# Schematic.net
KiCad netlist of a schematic drawn in Altium Designer
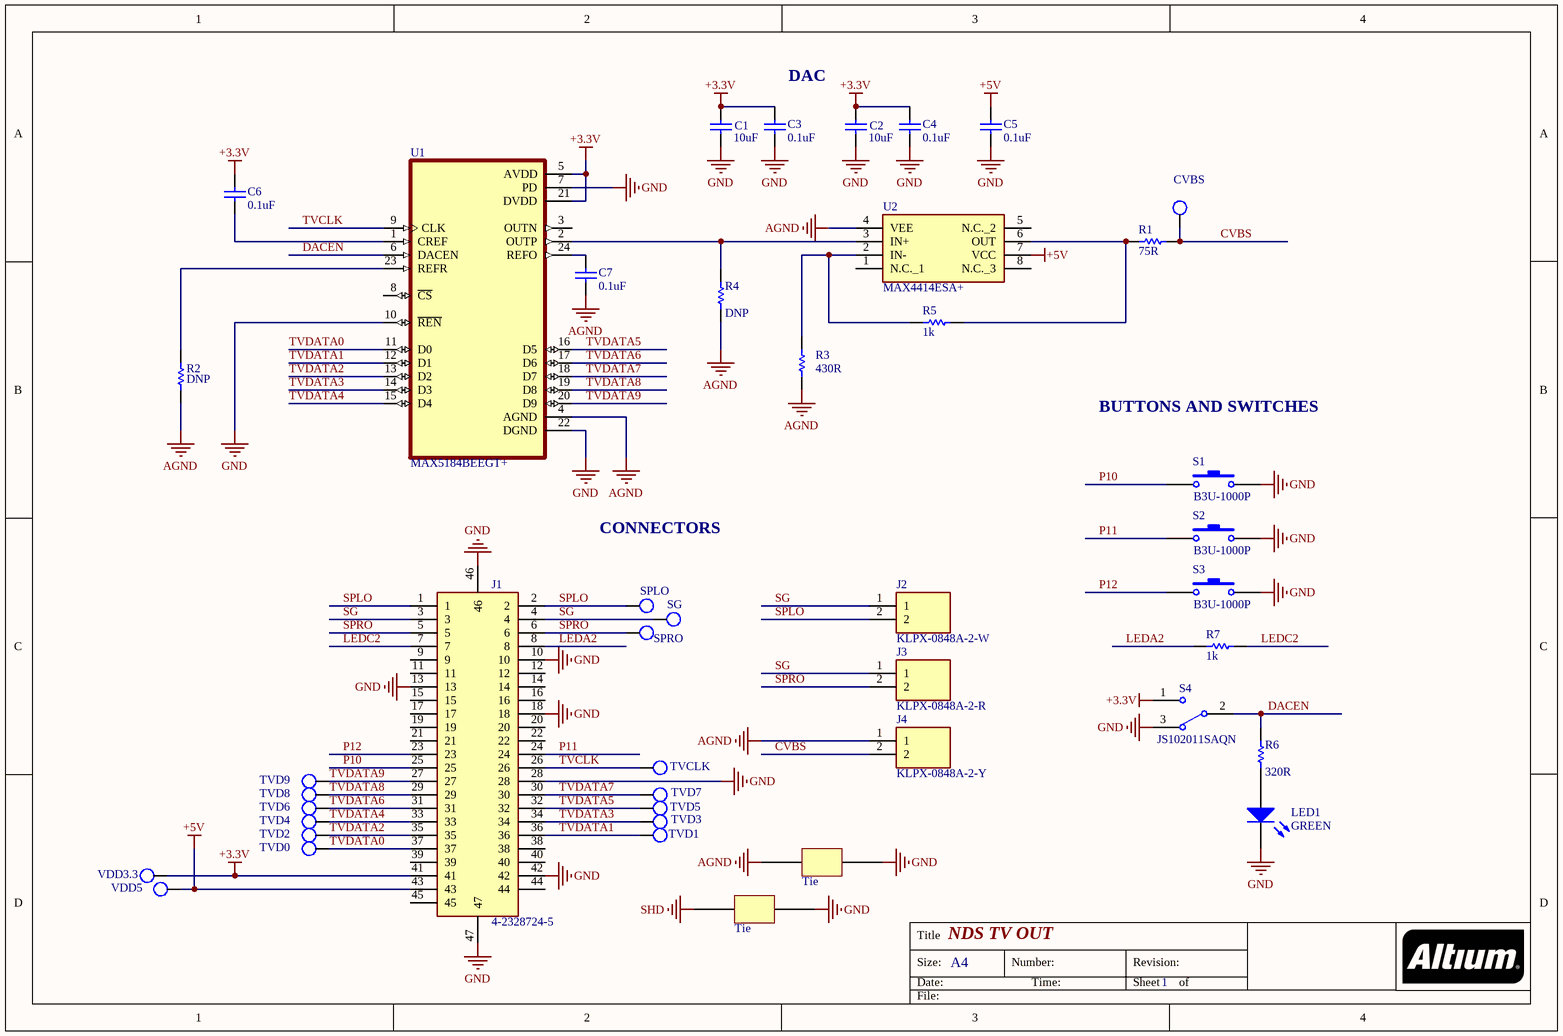
[diagram p0: Schematic.SchDoc]

(export (version "E")
  (design (tool "Eeschema 10.0.6"))
  (components
    (comp (ref "C1")
      (value "10uF")
      (footprint "CAPC2012X90N")
      (description "Capacitor")
      (fields (field (name "PUBLISHER") "Altium Limited"))
      (libsource (lib "Miscellaneous Devices") (part "Cap"))
    )
    (comp (ref "C2")
      (value "10uF")
      (footprint "CAPC2012X90N")
      (description "Capacitor")
      (fields (field (name "PUBLISHER") "Altium Limited"))
      (libsource (lib "Miscellaneous Devices") (part "Cap"))
    )
    (comp (ref "C3")
      (value "0.1uF")
      (footprint "CAPC2012X90N")
      (description "Capacitor")
      (fields (field (name "PUBLISHER") "Altium Limited"))
      (libsource (lib "Miscellaneous Devices") (part "Cap"))
    )
    (comp (ref "C4")
      (value "0.1uF")
      (footprint "CAPC2012X90N")
      (description "Capacitor")
      (fields (field (name "PUBLISHER") "Altium Limited"))
      (libsource (lib "Miscellaneous Devices") (part "Cap"))
    )
    (comp (ref "C5")
      (value "0.1uF")
      (footprint "CAPC2012X90N")
      (description "Capacitor")
      (fields (field (name "PUBLISHER") "Altium Limited"))
      (libsource (lib "Miscellaneous Devices") (part "Cap"))
    )
    (comp (ref "C6")
      (value "0.1uF")
      (footprint "CAPC2012X90N")
      (description "Capacitor")
      (fields (field (name "PUBLISHER") "Altium Limited"))
      (libsource (lib "Miscellaneous Devices") (part "Cap"))
    )
    (comp (ref "C7")
      (value "0.1uF")
      (footprint "CAPC2012X90N")
      (description "Capacitor")
      (fields (field (name "PUBLISHER") "Altium Limited"))
      (libsource (lib "Miscellaneous Devices") (part "Cap"))
    )
    (comp (ref "CVBS")
      (value "~")
      (footprint "Test_Point")
      (description "Test Point")
      (libsource (lib "*") (part "TP_P0_0.8_D0"))
    )
    (comp (ref "J1")
      (value "4-2328724-5")
      (footprint "SamacSys:423287245")
      (description "Connector")
      (fields (field (name "MOUSER PART NUMBER") "571-4-2328724-5"))
      (libsource (lib "*") (part "4-2328724-5"))
    )
    (comp (ref "J2")
      (value "KLPX-0848A-2-W")
      (footprint "SamacSys:KLPX0848A2RG")
      (description "Connector")
      (fields
        (field (name "MANUFACTURER_PART_NUMBER") "KLPX-0848A-2-R-G")
        (field (name "MOUSER PART NUMBER") "806-KLPX-0848A-2RG")
      )
      (libsource (lib "*") (part "KLPX-0848A-2-R-G"))
    )
    (comp (ref "J3")
      (value "KLPX-0848A-2-R")
      (footprint "SamacSys:KLPX0848A2RG")
      (description "Connector")
      (fields
        (field (name "MANUFACTURER_PART_NUMBER") "KLPX-0848A-2-R-G")
        (field (name "MOUSER PART NUMBER") "806-KLPX-0848A-2RG")
      )
      (libsource (lib "*") (part "KLPX-0848A-2-R-G"))
    )
    (comp (ref "J4")
      (value "KLPX-0848A-2-Y")
      (footprint "SamacSys:KLPX0848A2RG")
      (description "Connector")
      (fields
        (field (name "MANUFACTURER_PART_NUMBER") "KLPX-0848A-2-R-G")
        (field (name "MOUSER PART NUMBER") "806-KLPX-0848A-2RG")
      )
      (libsource (lib "*") (part "KLPX-0848A-2-R-G"))
    )
    (comp (ref "LED1")
      (value "GREEN")
      (footprint "LED_OSRAM_LOR976")
      (description "LED GREEN CLEAR 0603 SMD")
      (fields (field (name "MANUFACTURER") "Lite-On Inc.") (field (name "PUBLISHER") "Altium Limited"))
      (libsource (lib "Miscellaneous Devices") (part "LED0"))
    )
    (comp (ref "R1")
      (value "75R")
      (footprint "RESC2012X50N")
      (description "Resistor")
      (fields (field (name "Comment") "Res1") (field (name "PUBLISHER") "Altium Limited"))
      (libsource (lib "Miscellaneous Devices") (part "Res1"))
    )
    (comp (ref "R2")
      (value "DNP")
      (footprint "RESC2012X50N")
      (description "Resistor")
      (fields (field (name "Comment") "Res1") (field (name "PUBLISHER") "Altium Limited"))
      (libsource (lib "Miscellaneous Devices") (part "Res1"))
    )
    (comp (ref "R3")
      (value "430R")
      (footprint "RESC2012X50N")
      (description "Resistor")
      (fields (field (name "Comment") "Res1") (field (name "PUBLISHER") "Altium Limited"))
      (libsource (lib "Miscellaneous Devices") (part "Res1"))
    )
    (comp (ref "R4")
      (value "DNP")
      (footprint "RESC2012X50N")
      (description "Resistor")
      (fields (field (name "Comment") "Res1") (field (name "PUBLISHER") "Altium Limited"))
      (libsource (lib "Miscellaneous Devices") (part "Res1"))
    )
    (comp (ref "R5")
      (value "1k")
      (footprint "RESC2012X50N")
      (description "Resistor")
      (fields (field (name "Comment") "Res1") (field (name "PUBLISHER") "Altium Limited"))
      (libsource (lib "Miscellaneous Devices") (part "Res1"))
    )
    (comp (ref "R6")
      (value "320R")
      (footprint "RESC2012X50N")
      (description "Resistor")
      (fields (field (name "Comment") "Res1") (field (name "PUBLISHER") "Altium Limited"))
      (libsource (lib "Miscellaneous Devices") (part "Res1"))
    )
    (comp (ref "R7")
      (value "1k")
      (footprint "RESC2012X50N")
      (description "Resistor")
      (fields (field (name "Comment") "Res1") (field (name "PUBLISHER") "Altium Limited"))
      (libsource (lib "Miscellaneous Devices") (part "Res1"))
    )
    (comp (ref "S1")
      (value "B3U-1000P")
      (footprint "B3U-1000P")
      (description "Switch")
      (fields (field (name "PUBLISHER") "Altium Limited"))
      (libsource (lib "Miscellaneous Devices") (part "SW-PB"))
    )
    (comp (ref "S2")
      (value "B3U-1000P")
      (footprint "B3U-1000P")
      (description "Switch")
      (fields (field (name "PUBLISHER") "Altium Limited"))
      (libsource (lib "Miscellaneous Devices") (part "SW-PB"))
    )
    (comp (ref "S3")
      (value "B3U-1000P")
      (footprint "B3U-1000P")
      (description "Switch")
      (fields (field (name "PUBLISHER") "Altium Limited"))
      (libsource (lib "Miscellaneous Devices") (part "SW-PB"))
    )
    (comp (ref "S4")
      (value "JS102011SAQN")
      (footprint "JS102011SAQN")
      (description "SPDT Subminiature Toggle Switch, Right Angle Mounting, Vertical Actuation")
      (libsource (lib "Miscellaneous Devices") (part "SW-SPDT"))
    )
    (comp (ref "SG")
      (value "~")
      (footprint "Test_Point")
      (description "Test Point")
      (libsource (lib "*") (part "TP_P0_0.8_D0"))
    )
    (comp (ref "SPLO")
      (value "~")
      (footprint "Test_Point")
      (description "Test Point")
      (libsource (lib "*") (part "TP_P0_0.8_D0"))
    )
    (comp (ref "SPRO")
      (value "~")
      (footprint "Test_Point")
      (description "Test Point")
      (libsource (lib "*") (part "TP_P0_0.8_D0"))
    )
    (comp (ref "Tie1") (value "Tie") (footprint "Tie") (libsource (lib "MAX5184BEEGT") (part "Tie")))
    (comp (ref "Tie2") (value "Tie") (footprint "Tie") (libsource (lib "MAX5184BEEGT") (part "Tie")))
    (comp (ref "TVCLK")
      (value "~")
      (footprint "Test_Point")
      (description "Test Point")
      (libsource (lib "*") (part "TP_P0_0.8_D0"))
    )
    (comp (ref "TVD0")
      (value "~")
      (footprint "Test_Point")
      (description "Test Point")
      (libsource (lib "*") (part "TP_P0_0.8_D0"))
    )
    (comp (ref "TVD1")
      (value "~")
      (footprint "Test_Point")
      (description "Test Point")
      (libsource (lib "*") (part "TP_P0_0.8_D0"))
    )
    (comp (ref "TVD2")
      (value "~")
      (footprint "Test_Point")
      (description "Test Point")
      (libsource (lib "*") (part "TP_P0_0.8_D0"))
    )
    (comp (ref "TVD3")
      (value "~")
      (footprint "Test_Point")
      (description "Test Point")
      (libsource (lib "*") (part "TP_P0_0.8_D0"))
    )
    (comp (ref "TVD4")
      (value "~")
      (footprint "Test_Point")
      (description "Test Point")
      (libsource (lib "*") (part "TP_P0_0.8_D0"))
    )
    (comp (ref "TVD5")
      (value "~")
      (footprint "Test_Point")
      (description "Test Point")
      (libsource (lib "*") (part "TP_P0_0.8_D0"))
    )
    (comp (ref "TVD6")
      (value "~")
      (footprint "Test_Point")
      (description "Test Point")
      (libsource (lib "*") (part "TP_P0_0.8_D0"))
    )
    (comp (ref "TVD7")
      (value "~")
      (footprint "Test_Point")
      (description "Test Point")
      (libsource (lib "*") (part "TP_P0_0.8_D0"))
    )
    (comp (ref "TVD8")
      (value "~")
      (footprint "Test_Point")
      (description "Test Point")
      (libsource (lib "*") (part "TP_P0_0.8_D0"))
    )
    (comp (ref "TVD9")
      (value "~")
      (footprint "Test_Point")
      (description "Test Point")
      (libsource (lib "*") (part "TP_P0_0.8_D0"))
    )
    (comp (ref "U1")
      (value "MAX5184BEEGT+")
      (footprint "SOP63P602X175-24N")
      (fields (field (name "MP") "MAX5184BEEGT"))
      (libsource (lib "MAX5184BEEGT") (part "MAX5184BEEGT"))
    )
    (comp (ref "U2")
      (value "MAX4414ESA+")
      (footprint "SOIC127P600X175-8N")
      (description "Integrated Circuit")
      (fields (field (name "MOUSER PART NUMBER") "700-MAX4414ESA"))
      (libsource (lib "*") (part "MAX4414ESA+"))
    )
    (comp (ref "VDD3.3")
      (value "~")
      (footprint "Test_Point")
      (description "Test Point")
      (libsource (lib "*") (part "TP_P0_0.8_D0"))
    )
    (comp (ref "VDD5")
      (value "~")
      (footprint "Test_Point")
      (description "Test Point")
      (libsource (lib "*") (part "TP_P0_0.8_D0"))
    )
  )
  (nets
    (net (code "1") (name "+3.3V") (class "Default")
      (node (ref "C1") (pin "1") (pinfunction "1_1") (pintype "passive"))
      (node (ref "C2") (pin "1") (pinfunction "1_1") (pintype "passive"))
      (node (ref "C3") (pin "1") (pinfunction "1_1") (pintype "passive"))
      (node (ref "C4") (pin "1") (pinfunction "1_1") (pintype "passive"))
      (node (ref "C6") (pin "1") (pinfunction "1_1") (pintype "passive"))
      (node (ref "J1") (pin "41") (pinfunction "41_41") (pintype "passive"))
      (node (ref "S4") (pin "1") (pinfunction "1_1") (pintype "passive"))
      (node (ref "U1") (pin "21") (pinfunction "DVDD_21") (pintype "power_in"))
      (node (ref "U1") (pin "5") (pinfunction "AVDD_5") (pintype "power_in"))
      (node (ref "VDD3.3") (pin "1") (pinfunction "1_1") (pintype "passive"))
    )
    (net (code "2") (name "+5V") (class "Default")
      (node (ref "C5") (pin "1") (pinfunction "1_1") (pintype "passive"))
      (node (ref "J1") (pin "43") (pinfunction "43_43") (pintype "passive"))
      (node (ref "U2") (pin "7") (pinfunction "VCC_7") (pintype "passive"))
      (node (ref "VDD5") (pin "1") (pinfunction "1_1") (pintype "passive"))
    )
    (net (code "3") (name "/CVBS") (class "Default")
      (node (ref "CVBS") (pin "1") (pinfunction "1_1") (pintype "passive"))
      (node (ref "J4") (pin "2") (pinfunction "2_2") (pintype "passive"))
      (node (ref "R1") (pin "1") (pinfunction "1_1") (pintype "passive"))
    )
    (net (code "4") (name "/DACEN") (class "Default")
      (node (ref "R6") (pin "2") (pinfunction "2_2") (pintype "passive"))
      (node (ref "S4") (pin "2") (pinfunction "2_2") (pintype "passive"))
      (node (ref "U1") (pin "6") (pinfunction "DACEN_6") (pintype "input"))
    )
    (net (code "5") (name "/LEDA2") (class "Default")
      (node (ref "J1") (pin "8") (pinfunction "8_8") (pintype "passive"))
      (node (ref "R7") (pin "2") (pinfunction "2_2") (pintype "passive"))
    )
    (net (code "6") (name "/LEDC2") (class "Default")
      (node (ref "J1") (pin "7") (pinfunction "7_7") (pintype "passive"))
      (node (ref "R7") (pin "1") (pinfunction "1_1") (pintype "passive"))
    )
    (net (code "7") (name "/P10") (class "Default")
      (node (ref "J1") (pin "25") (pinfunction "25_25") (pintype "passive"))
      (node (ref "S1") (pin "1") (pinfunction "1_1") (pintype "passive"))
    )
    (net (code "8") (name "/P11") (class "Default")
      (node (ref "J1") (pin "24") (pinfunction "24_24") (pintype "passive"))
      (node (ref "S2") (pin "1") (pinfunction "1_1") (pintype "passive"))
    )
    (net (code "9") (name "/P12") (class "Default")
      (node (ref "J1") (pin "23") (pinfunction "23_23") (pintype "passive"))
      (node (ref "S3") (pin "1") (pinfunction "1_1") (pintype "passive"))
    )
    (net (code "10") (name "/SG") (class "Default")
      (node (ref "J1") (pin "3") (pinfunction "3_3") (pintype "passive"))
      (node (ref "J1") (pin "4") (pinfunction "4_4") (pintype "passive"))
      (node (ref "J2") (pin "1") (pinfunction "1_1") (pintype "passive"))
      (node (ref "J3") (pin "1") (pinfunction "1_1") (pintype "passive"))
      (node (ref "SG") (pin "1") (pinfunction "1_1") (pintype "passive"))
    )
    (net (code "11") (name "/SPLO") (class "Default")
      (node (ref "J1") (pin "1") (pinfunction "1_1") (pintype "passive"))
      (node (ref "J1") (pin "2") (pinfunction "2_2") (pintype "passive"))
      (node (ref "J2") (pin "2") (pinfunction "2_2") (pintype "passive"))
      (node (ref "SPLO") (pin "1") (pinfunction "1_1") (pintype "passive"))
    )
    (net (code "12") (name "/SPRO") (class "Default")
      (node (ref "J1") (pin "5") (pinfunction "5_5") (pintype "passive"))
      (node (ref "J1") (pin "6") (pinfunction "6_6") (pintype "passive"))
      (node (ref "J3") (pin "2") (pinfunction "2_2") (pintype "passive"))
      (node (ref "SPRO") (pin "1") (pinfunction "1_1") (pintype "passive"))
    )
    (net (code "13") (name "/TVCLK") (class "Default")
      (node (ref "J1") (pin "26") (pinfunction "26_26") (pintype "passive"))
      (node (ref "TVCLK") (pin "1") (pinfunction "1_1") (pintype "passive"))
      (node (ref "U1") (pin "9") (pinfunction "CLK_9") (pintype "input"))
    )
    (net (code "14") (name "/TVDATA0") (class "Default")
      (node (ref "J1") (pin "37") (pinfunction "37_37") (pintype "passive"))
      (node (ref "TVD0") (pin "1") (pinfunction "1_1") (pintype "passive"))
      (node (ref "U1") (pin "11") (pinfunction "D0_11") (pintype "bidirectional"))
    )
    (net (code "15") (name "/TVDATA1") (class "Default")
      (node (ref "J1") (pin "36") (pinfunction "36_36") (pintype "passive"))
      (node (ref "TVD1") (pin "1") (pinfunction "1_1") (pintype "passive"))
      (node (ref "U1") (pin "12") (pinfunction "D1_12") (pintype "bidirectional"))
    )
    (net (code "16") (name "/TVDATA2") (class "Default")
      (node (ref "J1") (pin "35") (pinfunction "35_35") (pintype "passive"))
      (node (ref "TVD2") (pin "1") (pinfunction "1_1") (pintype "passive"))
      (node (ref "U1") (pin "13") (pinfunction "D2_13") (pintype "bidirectional"))
    )
    (net (code "17") (name "/TVDATA3") (class "Default")
      (node (ref "J1") (pin "34") (pinfunction "34_34") (pintype "passive"))
      (node (ref "TVD3") (pin "1") (pinfunction "1_1") (pintype "passive"))
      (node (ref "U1") (pin "14") (pinfunction "D3_14") (pintype "bidirectional"))
    )
    (net (code "18") (name "/TVDATA4") (class "Default")
      (node (ref "J1") (pin "33") (pinfunction "33_33") (pintype "passive"))
      (node (ref "TVD4") (pin "1") (pinfunction "1_1") (pintype "passive"))
      (node (ref "U1") (pin "15") (pinfunction "D4_15") (pintype "bidirectional"))
    )
    (net (code "19") (name "/TVDATA5") (class "Default")
      (node (ref "J1") (pin "32") (pinfunction "32_32") (pintype "passive"))
      (node (ref "TVD5") (pin "1") (pinfunction "1_1") (pintype "passive"))
      (node (ref "U1") (pin "16") (pinfunction "D5_16") (pintype "bidirectional"))
    )
    (net (code "20") (name "/TVDATA6") (class "Default")
      (node (ref "J1") (pin "31") (pinfunction "31_31") (pintype "passive"))
      (node (ref "TVD6") (pin "1") (pinfunction "1_1") (pintype "passive"))
      (node (ref "U1") (pin "17") (pinfunction "D6_17") (pintype "bidirectional"))
    )
    (net (code "21") (name "/TVDATA7") (class "Default")
      (node (ref "J1") (pin "30") (pinfunction "30_30") (pintype "passive"))
      (node (ref "TVD7") (pin "1") (pinfunction "1_1") (pintype "passive"))
      (node (ref "U1") (pin "18") (pinfunction "D7_18") (pintype "bidirectional"))
    )
    (net (code "22") (name "/TVDATA8") (class "Default")
      (node (ref "J1") (pin "29") (pinfunction "29_29") (pintype "passive"))
      (node (ref "TVD8") (pin "1") (pinfunction "1_1") (pintype "passive"))
      (node (ref "U1") (pin "19") (pinfunction "D8_19") (pintype "bidirectional"))
    )
    (net (code "23") (name "/TVDATA9") (class "Default")
      (node (ref "J1") (pin "27") (pinfunction "27_27") (pintype "passive"))
      (node (ref "TVD9") (pin "1") (pinfunction "1_1") (pintype "passive"))
      (node (ref "U1") (pin "20") (pinfunction "D9_20") (pintype "bidirectional"))
    )
    (net (code "24") (name "AGND") (class "Default")
      (node (ref "C7") (pin "2") (pinfunction "2_2") (pintype "passive"))
      (node (ref "J4") (pin "1") (pinfunction "1_1") (pintype "passive"))
      (node (ref "R2") (pin "1") (pinfunction "1_1") (pintype "passive"))
      (node (ref "R3") (pin "1") (pinfunction "1_1") (pintype "passive"))
      (node (ref "R4") (pin "1") (pinfunction "1_1") (pintype "passive"))
      (node (ref "Tie1") (pin "1") (pinfunction "1_1") (pintype "passive"))
      (node (ref "U1") (pin "4") (pinfunction "AGND_4") (pintype "power_in"))
      (node (ref "U2") (pin "4") (pinfunction "VEE_4") (pintype "passive"))
    )
    (net (code "25") (name "GND") (class "Default")
      (node (ref "C1") (pin "2") (pinfunction "2_2") (pintype "passive"))
      (node (ref "C2") (pin "2") (pinfunction "2_2") (pintype "passive"))
      (node (ref "C3") (pin "2") (pinfunction "2_2") (pintype "passive"))
      (node (ref "C4") (pin "2") (pinfunction "2_2") (pintype "passive"))
      (node (ref "C5") (pin "2") (pinfunction "2_2") (pintype "passive"))
      (node (ref "J1") (pin "10") (pinfunction "10_10") (pintype "passive"))
      (node (ref "J1") (pin "13") (pinfunction "13_13") (pintype "passive"))
      (node (ref "J1") (pin "18") (pinfunction "18_18") (pintype "passive"))
      (node (ref "J1") (pin "28") (pinfunction "28_28") (pintype "passive"))
      (node (ref "J1") (pin "42") (pinfunction "42_42") (pintype "passive"))
      (node (ref "J1") (pin "46") (pinfunction "46_46") (pintype "passive"))
      (node (ref "J1") (pin "47") (pinfunction "47_47") (pintype "passive"))
      (node (ref "LED1") (pin "2") (pinfunction "K_2") (pintype "passive"))
      (node (ref "S1") (pin "2") (pinfunction "2_2") (pintype "passive"))
      (node (ref "S2") (pin "2") (pinfunction "2_2") (pintype "passive"))
      (node (ref "S3") (pin "2") (pinfunction "2_2") (pintype "passive"))
      (node (ref "S4") (pin "3") (pinfunction "3_3") (pintype "passive"))
      (node (ref "Tie1") (pin "2") (pinfunction "2_2") (pintype "passive"))
      (node (ref "Tie2") (pin "2") (pinfunction "2_2") (pintype "passive"))
      (node (ref "U1") (pin "10") (pinfunction "~{REN}_10") (pintype "bidirectional"))
      (node (ref "U1") (pin "22") (pinfunction "DGND_22") (pintype "power_in"))
      (node (ref "U1") (pin "7") (pinfunction "PD_7") (pintype "power_in"))
    )
    (net (code "26") (name "Net-(LED1-A)") (class "Default")
      (node (ref "LED1") (pin "1") (pinfunction "A_1") (pintype "passive"))
      (node (ref "R6") (pin "1") (pinfunction "1_1") (pintype "passive"))
    )
    (net (code "27") (name "Net-(U1-CREF)") (class "Default")
      (node (ref "C6") (pin "2") (pinfunction "2_2") (pintype "passive"))
      (node (ref "U1") (pin "1") (pinfunction "CREF_1") (pintype "input"))
    )
    (net (code "28") (name "Net-(U1-OUTP)") (class "Default")
      (node (ref "R4") (pin "2") (pinfunction "2_2") (pintype "passive"))
      (node (ref "U1") (pin "2") (pinfunction "OUTP_2") (pintype "output"))
      (node (ref "U2") (pin "3") (pinfunction "IN+_3") (pintype "passive"))
    )
    (net (code "29") (name "Net-(U1-REFO)") (class "Default")
      (node (ref "C7") (pin "1") (pinfunction "1_1") (pintype "passive"))
      (node (ref "U1") (pin "24") (pinfunction "REFO_24") (pintype "output"))
    )
    (net (code "30") (name "Net-(U1-REFR)") (class "Default")
      (node (ref "R2") (pin "2") (pinfunction "2_2") (pintype "passive"))
      (node (ref "U1") (pin "23") (pinfunction "REFR_23") (pintype "input"))
    )
    (net (code "31") (name "Net-(U2-IN-)") (class "Default")
      (node (ref "R3") (pin "2") (pinfunction "2_2") (pintype "passive"))
      (node (ref "R5") (pin "2") (pinfunction "2_2") (pintype "passive"))
      (node (ref "U2") (pin "2") (pinfunction "IN-_2") (pintype "passive"))
    )
    (net (code "32") (name "Net-(U2-OUT)") (class "Default")
      (node (ref "R1") (pin "2") (pinfunction "2_2") (pintype "passive"))
      (node (ref "R5") (pin "1") (pinfunction "1_1") (pintype "passive"))
      (node (ref "U2") (pin "6") (pinfunction "OUT_6") (pintype "passive"))
    )
    (net (code "33") (name "SHD") (class "Default")
      (node (ref "Tie2") (pin "1") (pinfunction "1_1") (pintype "passive"))
    )
    (net (code "34") (name "unconnected-(J1-Pad9)") (class "Default")
      (node (ref "J1") (pin "9") (pinfunction "9_9") (pintype "passive"))
    )
    (net (code "35") (name "unconnected-(J1-Pad11)") (class "Default")
      (node (ref "J1") (pin "11") (pinfunction "11_11") (pintype "passive"))
    )
    (net (code "36") (name "unconnected-(J1-Pad12)") (class "Default")
      (node (ref "J1") (pin "12") (pinfunction "12_12") (pintype "passive"))
    )
    (net (code "37") (name "unconnected-(J1-Pad14)") (class "Default")
      (node (ref "J1") (pin "14") (pinfunction "14_14") (pintype "passive"))
    )
    (net (code "38") (name "unconnected-(J1-Pad15)") (class "Default")
      (node (ref "J1") (pin "15") (pinfunction "15_15") (pintype "passive"))
    )
    (net (code "39") (name "unconnected-(J1-Pad16)") (class "Default")
      (node (ref "J1") (pin "16") (pinfunction "16_16") (pintype "passive"))
    )
    (net (code "40") (name "unconnected-(J1-Pad17)") (class "Default")
      (node (ref "J1") (pin "17") (pinfunction "17_17") (pintype "passive"))
    )
    (net (code "41") (name "unconnected-(J1-Pad19)") (class "Default")
      (node (ref "J1") (pin "19") (pinfunction "19_19") (pintype "passive"))
    )
    (net (code "42") (name "unconnected-(J1-Pad20)") (class "Default")
      (node (ref "J1") (pin "20") (pinfunction "20_20") (pintype "passive"))
    )
    (net (code "43") (name "unconnected-(J1-Pad21)") (class "Default")
      (node (ref "J1") (pin "21") (pinfunction "21_21") (pintype "passive"))
    )
    (net (code "44") (name "unconnected-(J1-Pad22)") (class "Default")
      (node (ref "J1") (pin "22") (pinfunction "22_22") (pintype "passive"))
    )
    (net (code "45") (name "unconnected-(J1-Pad38)") (class "Default")
      (node (ref "J1") (pin "38") (pinfunction "38_38") (pintype "passive"))
    )
    (net (code "46") (name "unconnected-(J1-Pad39)") (class "Default")
      (node (ref "J1") (pin "39") (pinfunction "39_39") (pintype "passive"))
    )
    (net (code "47") (name "unconnected-(J1-Pad40)") (class "Default")
      (node (ref "J1") (pin "40") (pinfunction "40_40") (pintype "passive"))
    )
    (net (code "48") (name "unconnected-(J1-Pad44)") (class "Default")
      (node (ref "J1") (pin "44") (pinfunction "44_44") (pintype "passive"))
    )
    (net (code "49") (name "unconnected-(J1-Pad45)") (class "Default")
      (node (ref "J1") (pin "45") (pinfunction "45_45") (pintype "passive"))
    )
    (net (code "50") (name "unconnected-(U1-OUTN-Pad3)") (class "Default")
      (node (ref "U1") (pin "3") (pinfunction "OUTN_3") (pintype "output"))
    )
    (net (code "51") (name "unconnected-(U1-~{CS}-Pad8)") (class "Default")
      (node (ref "U1") (pin "8") (pinfunction "~{CS}_8") (pintype "bidirectional"))
    )
    (net (code "52") (name "unconnected-(U2-N.C._1-Pad1)") (class "Default")
      (node (ref "U2") (pin "1") (pinfunction "N.C._1_1") (pintype "passive"))
    )
    (net (code "53") (name "unconnected-(U2-N.C._2-Pad5)") (class "Default")
      (node (ref "U2") (pin "5") (pinfunction "N.C._2_5") (pintype "passive"))
    )
    (net (code "54") (name "unconnected-(U2-N.C._3-Pad8)") (class "Default")
      (node (ref "U2") (pin "8") (pinfunction "N.C._3_8") (pintype "passive"))
    )
  )
)
